# Microcontroller_board_Photodiode_plate.net
KiCad netlist of a schematic drawn in EasyEDA
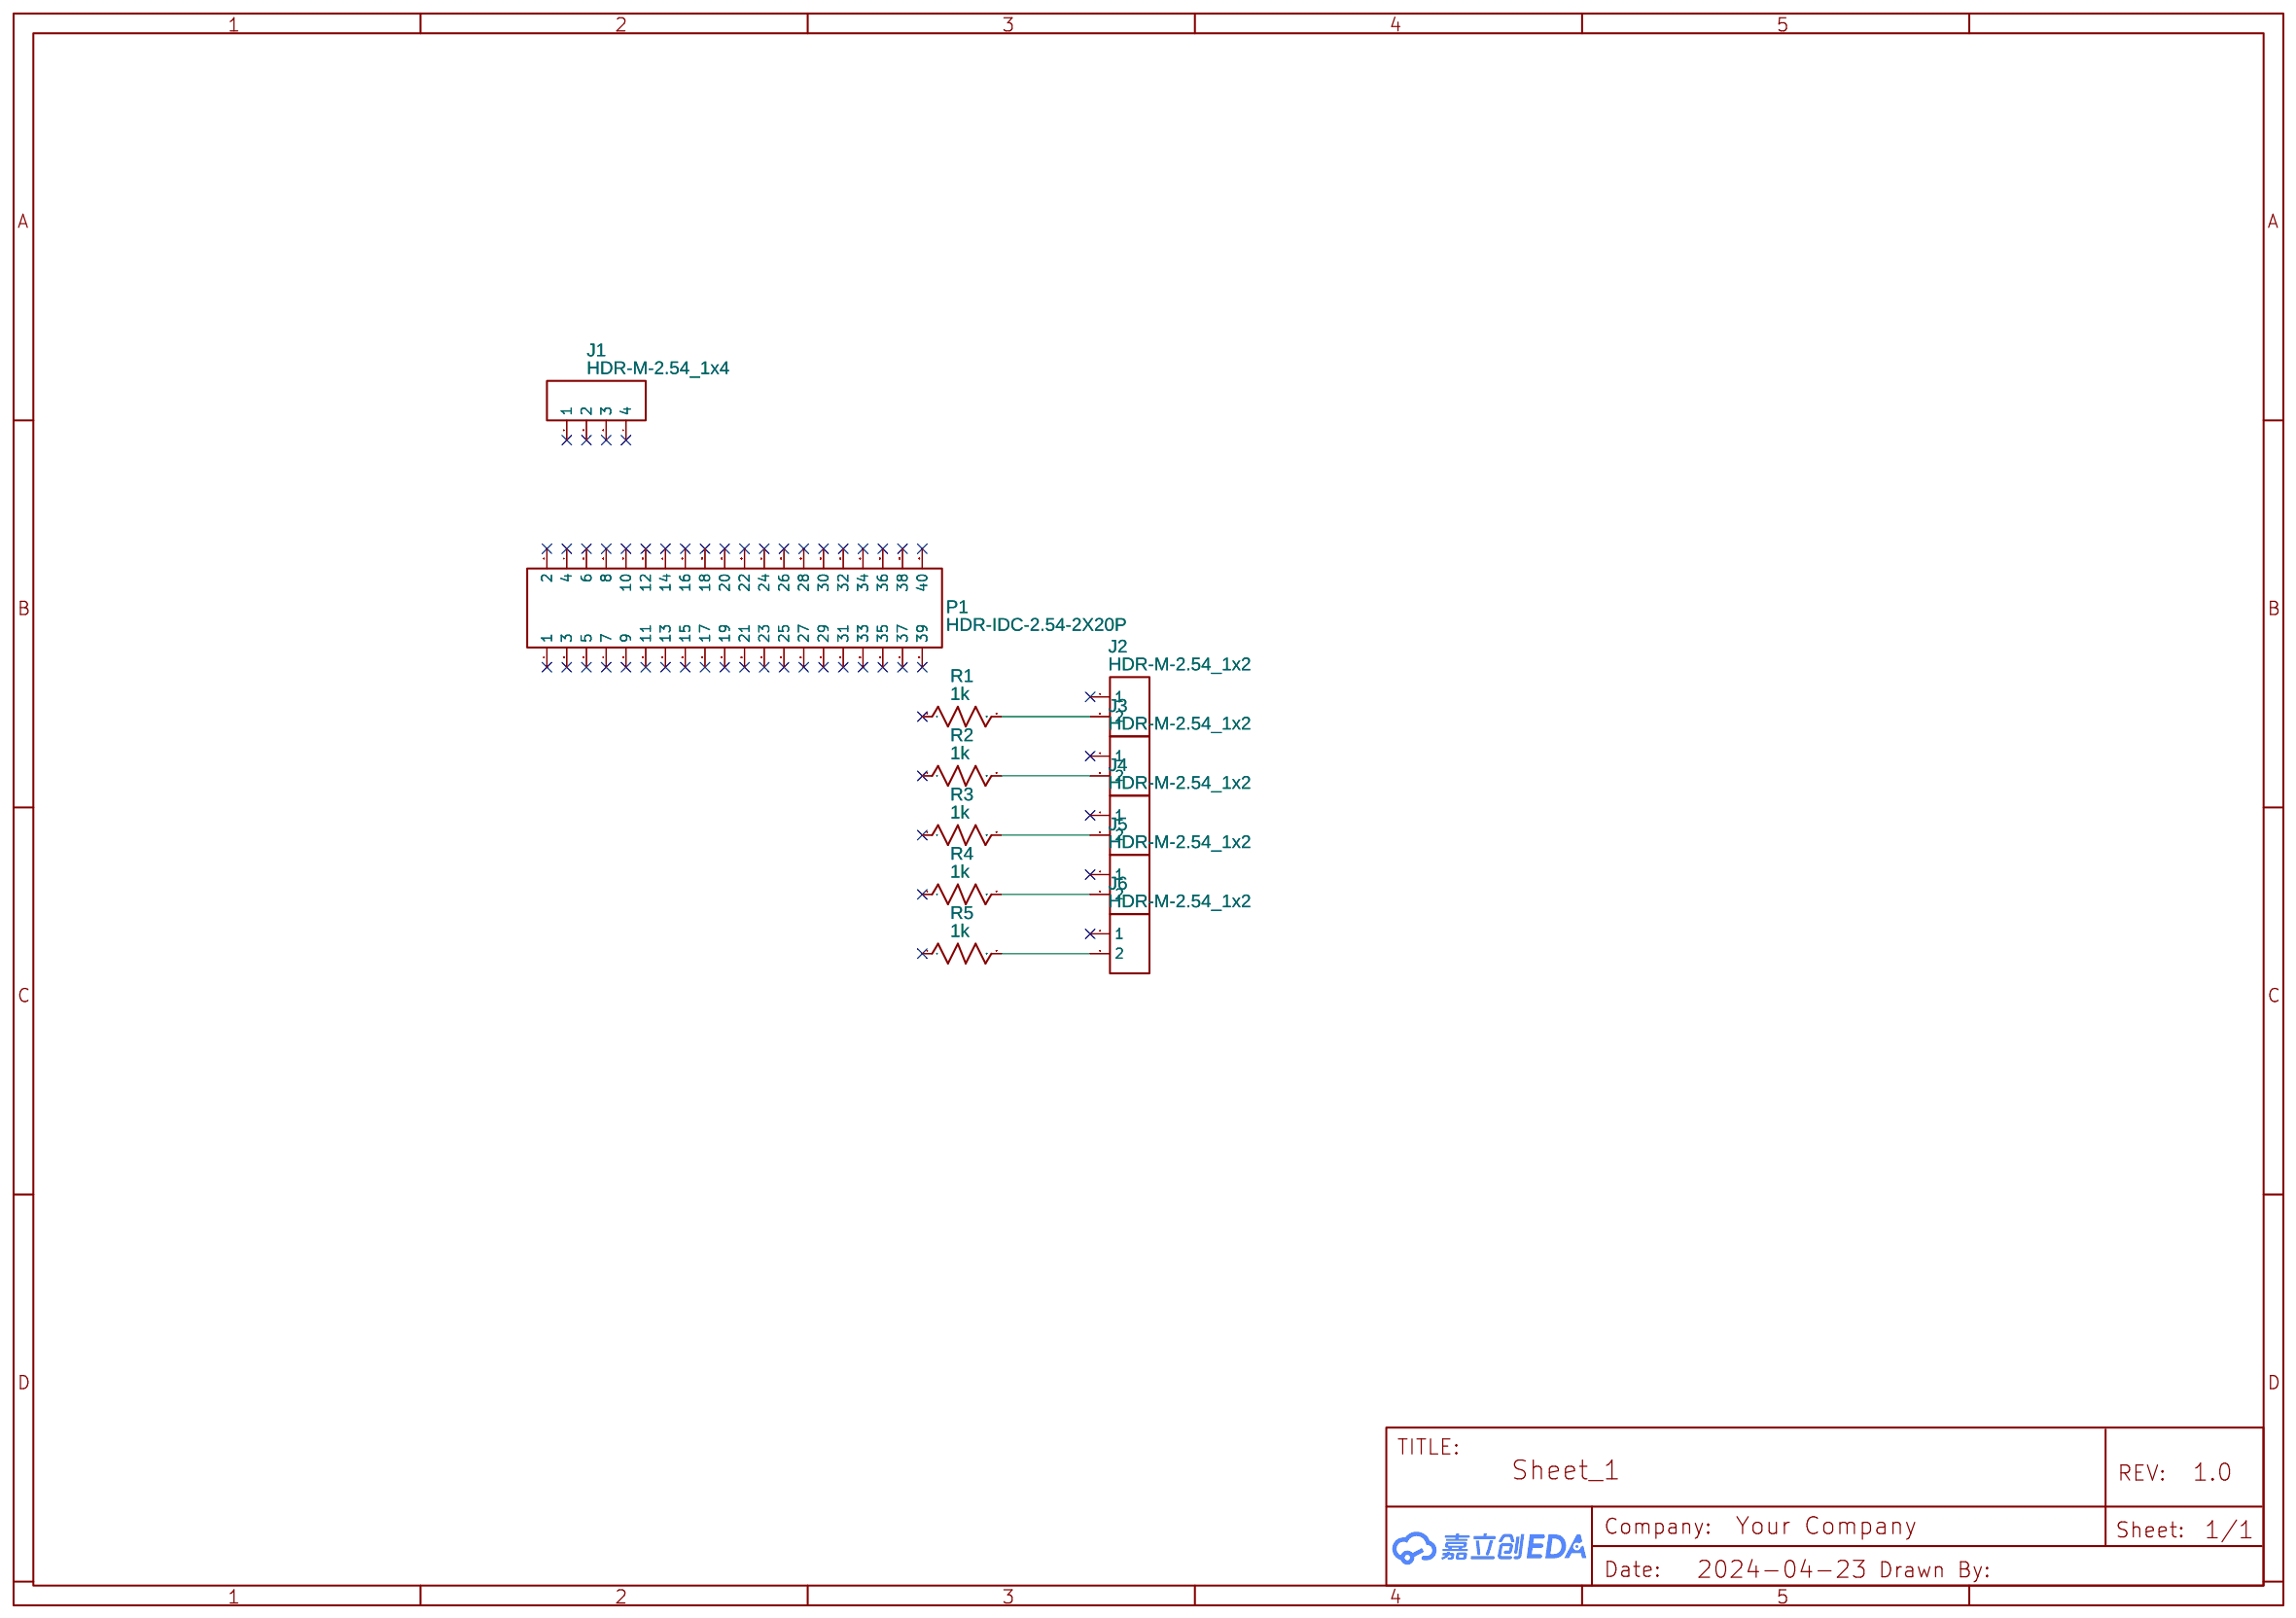
[diagram p0: schematic sheet]

(export (version "E")
  (design (tool "Eeschema 10.0.6"))
  (components
    (comp (ref "J1")
      (value "HDR-M-2.54_1x4")
      (fields (field (name "BOM_Supplier Part") "C124378"))
      (libsource (lib "") (part "HDR-M-2.54_1x4"))
    )
    (comp (ref "J2")
      (value "HDR-M-2.54_1x2")
      (fields (field (name "BOM_Supplier Part") "C124375"))
      (libsource (lib "") (part "HDR-M-2.54_1x2"))
    )
    (comp (ref "J3")
      (value "HDR-M-2.54_1x2")
      (fields (field (name "BOM_Supplier Part") "C124375"))
      (libsource (lib "") (part "HDR-M-2.54_1x2"))
    )
    (comp (ref "J4")
      (value "HDR-M-2.54_1x2")
      (fields (field (name "BOM_Supplier Part") "C124375"))
      (libsource (lib "") (part "HDR-M-2.54_1x2"))
    )
    (comp (ref "J5")
      (value "HDR-M-2.54_1x2")
      (fields (field (name "BOM_Supplier Part") "C124375"))
      (libsource (lib "") (part "HDR-M-2.54_1x2"))
    )
    (comp (ref "J6")
      (value "HDR-M-2.54_1x2")
      (fields (field (name "BOM_Supplier Part") "C124375"))
      (libsource (lib "") (part "HDR-M-2.54_1x2"))
    )
    (comp (ref "P1")
      (value "HDR-IDC-2.54-2X20P")
      (fields
        (field (name "BOM_Manufacturer Part") "IDC Box 2X20 2.54MM")
        (field (name "BOM_Supplier Part") "C9138")
      )
      (libsource (lib "") (part "HDR-IDC-2.54-2X20P"))
    )
    (comp (ref "R1") (value "1k") (libsource (lib "") (part "R_AXIAL-0.3_US")))
    (comp (ref "R2") (value "1k") (libsource (lib "") (part "R_AXIAL-0.3_US")))
    (comp (ref "R3") (value "1k") (libsource (lib "") (part "R_AXIAL-0.3_US")))
    (comp (ref "R4") (value "1k") (libsource (lib "") (part "R_AXIAL-0.3_US")))
    (comp (ref "R5") (value "1k") (libsource (lib "") (part "R_AXIAL-0.3_US")))
  )
  (nets
    (net (code "1") (name "Net-(J2-Pad2)") (class "Default")
      (node (ref "J2") (pin "2") (pinfunction "2_2") (pintype "unspecified"))
      (node (ref "R1") (pin "2") (pinfunction "2_2") (pintype "unspecified"))
    )
    (net (code "2") (name "Net-(J3-Pad2)") (class "Default")
      (node (ref "J3") (pin "2") (pinfunction "2_2") (pintype "unspecified"))
      (node (ref "R2") (pin "2") (pinfunction "2_2") (pintype "unspecified"))
    )
    (net (code "3") (name "Net-(J4-Pad2)") (class "Default")
      (node (ref "J4") (pin "2") (pinfunction "2_2") (pintype "unspecified"))
      (node (ref "R3") (pin "2") (pinfunction "2_2") (pintype "unspecified"))
    )
    (net (code "4") (name "Net-(J5-Pad2)") (class "Default")
      (node (ref "J5") (pin "2") (pinfunction "2_2") (pintype "unspecified"))
      (node (ref "R4") (pin "2") (pinfunction "2_2") (pintype "unspecified"))
    )
    (net (code "5") (name "Net-(J6-Pad2)") (class "Default")
      (node (ref "J6") (pin "2") (pinfunction "2_2") (pintype "unspecified"))
      (node (ref "R5") (pin "2") (pinfunction "2_2") (pintype "unspecified"))
    )
    (net (code "6") (name "unconnected-(J1-Pad1)") (class "Default")
      (node (ref "J1") (pin "1") (pinfunction "1_1") (pintype "unspecified+no_connect"))
    )
    (net (code "7") (name "unconnected-(J1-Pad2)") (class "Default")
      (node (ref "J1") (pin "2") (pinfunction "2_2") (pintype "unspecified+no_connect"))
    )
    (net (code "8") (name "unconnected-(J1-Pad3)") (class "Default")
      (node (ref "J1") (pin "3") (pinfunction "3_3") (pintype "unspecified+no_connect"))
    )
    (net (code "9") (name "unconnected-(J1-Pad4)") (class "Default")
      (node (ref "J1") (pin "4") (pinfunction "4_4") (pintype "unspecified+no_connect"))
    )
    (net (code "10") (name "unconnected-(J2-Pad1)") (class "Default")
      (node (ref "J2") (pin "1") (pinfunction "1_1") (pintype "unspecified+no_connect"))
    )
    (net (code "11") (name "unconnected-(J3-Pad1)") (class "Default")
      (node (ref "J3") (pin "1") (pinfunction "1_1") (pintype "unspecified+no_connect"))
    )
    (net (code "12") (name "unconnected-(J4-Pad1)") (class "Default")
      (node (ref "J4") (pin "1") (pinfunction "1_1") (pintype "unspecified+no_connect"))
    )
    (net (code "13") (name "unconnected-(J5-Pad1)") (class "Default")
      (node (ref "J5") (pin "1") (pinfunction "1_1") (pintype "unspecified+no_connect"))
    )
    (net (code "14") (name "unconnected-(J6-Pad1)") (class "Default")
      (node (ref "J6") (pin "1") (pinfunction "1_1") (pintype "unspecified+no_connect"))
    )
    (net (code "15") (name "unconnected-(P1-Pad1)") (class "Default")
      (node (ref "P1") (pin "1") (pinfunction "1_1") (pintype "unspecified+no_connect"))
    )
    (net (code "16") (name "unconnected-(P1-Pad2)") (class "Default")
      (node (ref "P1") (pin "2") (pinfunction "2_2") (pintype "unspecified+no_connect"))
    )
    (net (code "17") (name "unconnected-(P1-Pad3)") (class "Default")
      (node (ref "P1") (pin "3") (pinfunction "3_3") (pintype "unspecified+no_connect"))
    )
    (net (code "18") (name "unconnected-(P1-Pad4)") (class "Default")
      (node (ref "P1") (pin "4") (pinfunction "4_4") (pintype "unspecified+no_connect"))
    )
    (net (code "19") (name "unconnected-(P1-Pad5)") (class "Default")
      (node (ref "P1") (pin "5") (pinfunction "5_5") (pintype "unspecified+no_connect"))
    )
    (net (code "20") (name "unconnected-(P1-Pad6)") (class "Default")
      (node (ref "P1") (pin "6") (pinfunction "6_6") (pintype "unspecified+no_connect"))
    )
    (net (code "21") (name "unconnected-(P1-Pad7)") (class "Default")
      (node (ref "P1") (pin "7") (pinfunction "7_7") (pintype "unspecified+no_connect"))
    )
    (net (code "22") (name "unconnected-(P1-Pad8)") (class "Default")
      (node (ref "P1") (pin "8") (pinfunction "8_8") (pintype "unspecified+no_connect"))
    )
    (net (code "23") (name "unconnected-(P1-Pad9)") (class "Default")
      (node (ref "P1") (pin "9") (pinfunction "9_9") (pintype "unspecified+no_connect"))
    )
    (net (code "24") (name "unconnected-(P1-Pad10)") (class "Default")
      (node (ref "P1") (pin "10") (pinfunction "10_10") (pintype "unspecified+no_connect"))
    )
    (net (code "25") (name "unconnected-(P1-Pad11)") (class "Default")
      (node (ref "P1") (pin "11") (pinfunction "11_11") (pintype "unspecified+no_connect"))
    )
    (net (code "26") (name "unconnected-(P1-Pad12)") (class "Default")
      (node (ref "P1") (pin "12") (pinfunction "12_12") (pintype "unspecified+no_connect"))
    )
    (net (code "27") (name "unconnected-(P1-Pad13)") (class "Default")
      (node (ref "P1") (pin "13") (pinfunction "13_13") (pintype "unspecified+no_connect"))
    )
    (net (code "28") (name "unconnected-(P1-Pad14)") (class "Default")
      (node (ref "P1") (pin "14") (pinfunction "14_14") (pintype "unspecified+no_connect"))
    )
    (net (code "29") (name "unconnected-(P1-Pad15)") (class "Default")
      (node (ref "P1") (pin "15") (pinfunction "15_15") (pintype "unspecified+no_connect"))
    )
    (net (code "30") (name "unconnected-(P1-Pad16)") (class "Default")
      (node (ref "P1") (pin "16") (pinfunction "16_16") (pintype "unspecified+no_connect"))
    )
    (net (code "31") (name "unconnected-(P1-Pad17)") (class "Default")
      (node (ref "P1") (pin "17") (pinfunction "17_17") (pintype "unspecified+no_connect"))
    )
    (net (code "32") (name "unconnected-(P1-Pad18)") (class "Default")
      (node (ref "P1") (pin "18") (pinfunction "18_18") (pintype "unspecified+no_connect"))
    )
    (net (code "33") (name "unconnected-(P1-Pad19)") (class "Default")
      (node (ref "P1") (pin "19") (pinfunction "19_19") (pintype "unspecified+no_connect"))
    )
    (net (code "34") (name "unconnected-(P1-Pad20)") (class "Default")
      (node (ref "P1") (pin "20") (pinfunction "20_20") (pintype "unspecified+no_connect"))
    )
    (net (code "35") (name "unconnected-(P1-Pad21)") (class "Default")
      (node (ref "P1") (pin "21") (pinfunction "21_21") (pintype "unspecified+no_connect"))
    )
    (net (code "36") (name "unconnected-(P1-Pad22)") (class "Default")
      (node (ref "P1") (pin "22") (pinfunction "22_22") (pintype "unspecified+no_connect"))
    )
    (net (code "37") (name "unconnected-(P1-Pad23)") (class "Default")
      (node (ref "P1") (pin "23") (pinfunction "23_23") (pintype "unspecified+no_connect"))
    )
    (net (code "38") (name "unconnected-(P1-Pad24)") (class "Default")
      (node (ref "P1") (pin "24") (pinfunction "24_24") (pintype "unspecified+no_connect"))
    )
    (net (code "39") (name "unconnected-(P1-Pad25)") (class "Default")
      (node (ref "P1") (pin "25") (pinfunction "25_25") (pintype "unspecified+no_connect"))
    )
    (net (code "40") (name "unconnected-(P1-Pad26)") (class "Default")
      (node (ref "P1") (pin "26") (pinfunction "26_26") (pintype "unspecified+no_connect"))
    )
    (net (code "41") (name "unconnected-(P1-Pad27)") (class "Default")
      (node (ref "P1") (pin "27") (pinfunction "27_27") (pintype "unspecified+no_connect"))
    )
    (net (code "42") (name "unconnected-(P1-Pad28)") (class "Default")
      (node (ref "P1") (pin "28") (pinfunction "28_28") (pintype "unspecified+no_connect"))
    )
    (net (code "43") (name "unconnected-(P1-Pad29)") (class "Default")
      (node (ref "P1") (pin "29") (pinfunction "29_29") (pintype "unspecified+no_connect"))
    )
    (net (code "44") (name "unconnected-(P1-Pad30)") (class "Default")
      (node (ref "P1") (pin "30") (pinfunction "30_30") (pintype "unspecified+no_connect"))
    )
    (net (code "45") (name "unconnected-(P1-Pad31)") (class "Default")
      (node (ref "P1") (pin "31") (pinfunction "31_31") (pintype "unspecified+no_connect"))
    )
    (net (code "46") (name "unconnected-(P1-Pad32)") (class "Default")
      (node (ref "P1") (pin "32") (pinfunction "32_32") (pintype "unspecified+no_connect"))
    )
    (net (code "47") (name "unconnected-(P1-Pad33)") (class "Default")
      (node (ref "P1") (pin "33") (pinfunction "33_33") (pintype "unspecified+no_connect"))
    )
    (net (code "48") (name "unconnected-(P1-Pad34)") (class "Default")
      (node (ref "P1") (pin "34") (pinfunction "34_34") (pintype "unspecified+no_connect"))
    )
    (net (code "49") (name "unconnected-(P1-Pad35)") (class "Default")
      (node (ref "P1") (pin "35") (pinfunction "35_35") (pintype "unspecified+no_connect"))
    )
    (net (code "50") (name "unconnected-(P1-Pad36)") (class "Default")
      (node (ref "P1") (pin "36") (pinfunction "36_36") (pintype "unspecified+no_connect"))
    )
    (net (code "51") (name "unconnected-(P1-Pad37)") (class "Default")
      (node (ref "P1") (pin "37") (pinfunction "37_37") (pintype "unspecified+no_connect"))
    )
    (net (code "52") (name "unconnected-(P1-Pad38)") (class "Default")
      (node (ref "P1") (pin "38") (pinfunction "38_38") (pintype "unspecified+no_connect"))
    )
    (net (code "53") (name "unconnected-(P1-Pad39)") (class "Default")
      (node (ref "P1") (pin "39") (pinfunction "39_39") (pintype "unspecified+no_connect"))
    )
    (net (code "54") (name "unconnected-(P1-Pad40)") (class "Default")
      (node (ref "P1") (pin "40") (pinfunction "40_40") (pintype "unspecified+no_connect"))
    )
    (net (code "55") (name "unconnected-(R1-Pad1)") (class "Default")
      (node (ref "R1") (pin "1") (pinfunction "1_1") (pintype "unspecified+no_connect"))
    )
    (net (code "56") (name "unconnected-(R2-Pad1)") (class "Default")
      (node (ref "R2") (pin "1") (pinfunction "1_1") (pintype "unspecified+no_connect"))
    )
    (net (code "57") (name "unconnected-(R3-Pad1)") (class "Default")
      (node (ref "R3") (pin "1") (pinfunction "1_1") (pintype "unspecified+no_connect"))
    )
    (net (code "58") (name "unconnected-(R4-Pad1)") (class "Default")
      (node (ref "R4") (pin "1") (pinfunction "1_1") (pintype "unspecified+no_connect"))
    )
    (net (code "59") (name "unconnected-(R5-Pad1)") (class "Default")
      (node (ref "R5") (pin "1") (pinfunction "1_1") (pintype "unspecified+no_connect"))
    )
  )
)
